# Sheet2_old.net
KiCad netlist of a schematic drawn in Altium Designer
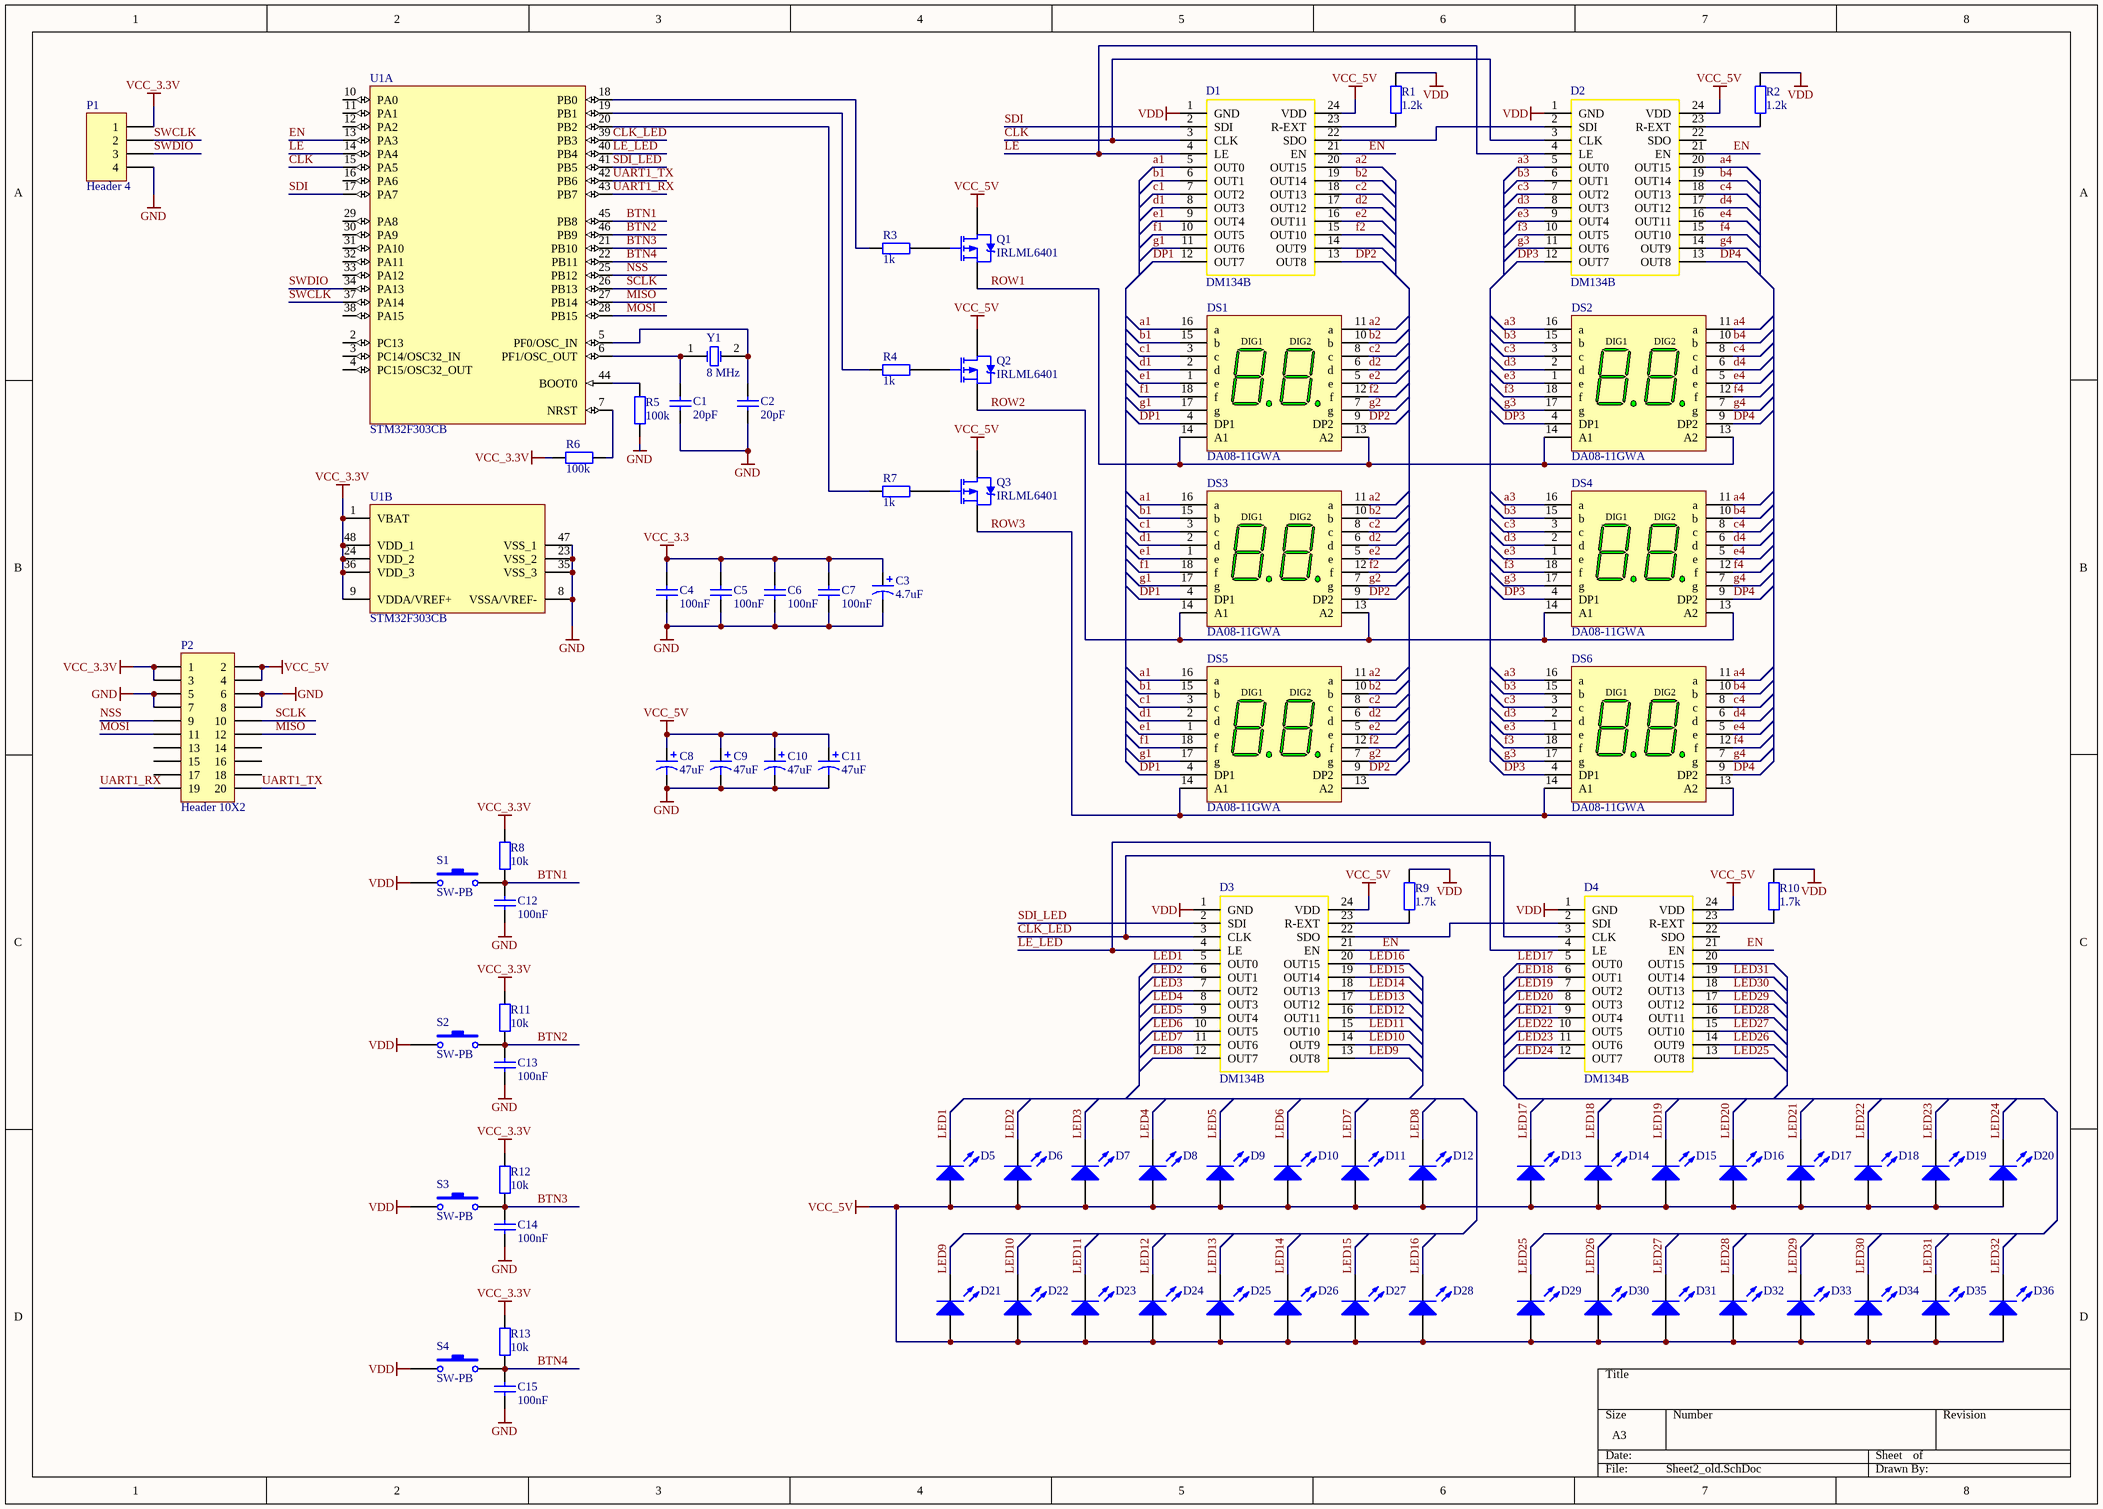
[diagram p0: Sheet2_old.SchDoc]

(export (version "E")
  (design (tool "Eeschema 10.0.6"))
  (components
    (comp (ref "C1")
      (value "20pF")
      (footprint "RAD-0.3")
      (description "Capacitor")
      (fields (field (name "PUBLISHER") "Altium Limited"))
      (libsource (lib "Miscellaneous Devices") (part "Cap"))
    )
    (comp (ref "C2")
      (value "20pF")
      (footprint "RAD-0.3")
      (description "Capacitor")
      (fields (field (name "PUBLISHER") "Altium Limited"))
      (libsource (lib "Miscellaneous Devices") (part "Cap"))
    )
    (comp (ref "C3")
      (value "4.7uF")
      (footprint "RB7.6-15")
      (description "Polarized Capacitor (Radial)")
      (fields (field (name "PUBLISHER") "Altium Limited"))
      (libsource (lib "Miscellaneous Devices") (part "Cap Pol1"))
    )
    (comp (ref "C4")
      (value "100nF")
      (footprint "RAD-0.3")
      (description "Capacitor")
      (fields (field (name "PUBLISHER") "Altium Limited"))
      (libsource (lib "Miscellaneous Devices") (part "Cap"))
    )
    (comp (ref "C5")
      (value "100nF")
      (footprint "RAD-0.3")
      (description "Capacitor")
      (fields (field (name "PUBLISHER") "Altium Limited"))
      (libsource (lib "Miscellaneous Devices") (part "Cap"))
    )
    (comp (ref "C6")
      (value "100nF")
      (footprint "RAD-0.3")
      (description "Capacitor")
      (fields (field (name "PUBLISHER") "Altium Limited"))
      (libsource (lib "Miscellaneous Devices") (part "Cap"))
    )
    (comp (ref "C7")
      (value "100nF")
      (footprint "RAD-0.3")
      (description "Capacitor")
      (fields (field (name "PUBLISHER") "Altium Limited"))
      (libsource (lib "Miscellaneous Devices") (part "Cap"))
    )
    (comp (ref "C8")
      (value "47uF")
      (footprint "RB7.6-15")
      (description "Polarized Capacitor (Radial)")
      (fields (field (name "PUBLISHER") "Altium Limited"))
      (libsource (lib "Miscellaneous Devices") (part "Cap Pol1"))
    )
    (comp (ref "C9")
      (value "47uF")
      (footprint "RB7.6-15")
      (description "Polarized Capacitor (Radial)")
      (fields (field (name "PUBLISHER") "Altium Limited"))
      (libsource (lib "Miscellaneous Devices") (part "Cap Pol1"))
    )
    (comp (ref "C10")
      (value "47uF")
      (footprint "RB7.6-15")
      (description "Polarized Capacitor (Radial)")
      (fields (field (name "PUBLISHER") "Altium Limited"))
      (libsource (lib "Miscellaneous Devices") (part "Cap Pol1"))
    )
    (comp (ref "C11")
      (value "47uF")
      (footprint "RB7.6-15")
      (description "Polarized Capacitor (Radial)")
      (fields (field (name "PUBLISHER") "Altium Limited"))
      (libsource (lib "Miscellaneous Devices") (part "Cap Pol1"))
    )
    (comp (ref "C12")
      (value "100nF")
      (footprint "RAD-0.3")
      (description "Capacitor")
      (fields (field (name "PUBLISHER") "Altium Limited"))
      (libsource (lib "Miscellaneous Devices") (part "Cap"))
    )
    (comp (ref "C13")
      (value "100nF")
      (footprint "RAD-0.3")
      (description "Capacitor")
      (fields (field (name "PUBLISHER") "Altium Limited"))
      (libsource (lib "Miscellaneous Devices") (part "Cap"))
    )
    (comp (ref "C14")
      (value "100nF")
      (footprint "RAD-0.3")
      (description "Capacitor")
      (fields (field (name "PUBLISHER") "Altium Limited"))
      (libsource (lib "Miscellaneous Devices") (part "Cap"))
    )
    (comp (ref "C15")
      (value "100nF")
      (footprint "RAD-0.3")
      (description "Capacitor")
      (fields (field (name "PUBLISHER") "Altium Limited"))
      (libsource (lib "Miscellaneous Devices") (part "Cap"))
    )
    (comp (ref "D1")
      (value "DM134B")
      (description "LED Driver")
      (libsource (lib "Sektor_LED_Drivers") (part "DM134B"))
    )
    (comp (ref "D2")
      (value "DM134B")
      (description "LED Driver")
      (libsource (lib "Sektor_LED_Drivers") (part "DM134B"))
    )
    (comp (ref "D3")
      (value "DM134B")
      (description "LED Driver")
      (libsource (lib "Sektor_LED_Drivers") (part "DM134B"))
    )
    (comp (ref "D4")
      (value "DM134B")
      (description "LED Driver")
      (libsource (lib "Sektor_LED_Drivers") (part "DM134B"))
    )
    (comp (ref "D5")
      (value "LED0")
      (footprint "LED-0")
      (description "Typical INFRARED GaAs LED")
      (fields (field (name "PUBLISHER") "Altium Limited"))
      (libsource (lib "Miscellaneous Devices") (part "LED0"))
    )
    (comp (ref "D6")
      (value "LED0")
      (footprint "LED-0")
      (description "Typical INFRARED GaAs LED")
      (fields (field (name "PUBLISHER") "Altium Limited"))
      (libsource (lib "Miscellaneous Devices") (part "LED0"))
    )
    (comp (ref "D7")
      (value "LED0")
      (footprint "LED-0")
      (description "Typical INFRARED GaAs LED")
      (fields (field (name "PUBLISHER") "Altium Limited"))
      (libsource (lib "Miscellaneous Devices") (part "LED0"))
    )
    (comp (ref "D8")
      (value "LED0")
      (footprint "LED-0")
      (description "Typical INFRARED GaAs LED")
      (fields (field (name "PUBLISHER") "Altium Limited"))
      (libsource (lib "Miscellaneous Devices") (part "LED0"))
    )
    (comp (ref "D9")
      (value "LED0")
      (footprint "LED-0")
      (description "Typical INFRARED GaAs LED")
      (fields (field (name "PUBLISHER") "Altium Limited"))
      (libsource (lib "Miscellaneous Devices") (part "LED0"))
    )
    (comp (ref "D10")
      (value "LED0")
      (footprint "LED-0")
      (description "Typical INFRARED GaAs LED")
      (fields (field (name "PUBLISHER") "Altium Limited"))
      (libsource (lib "Miscellaneous Devices") (part "LED0"))
    )
    (comp (ref "D11")
      (value "LED0")
      (footprint "LED-0")
      (description "Typical INFRARED GaAs LED")
      (fields (field (name "PUBLISHER") "Altium Limited"))
      (libsource (lib "Miscellaneous Devices") (part "LED0"))
    )
    (comp (ref "D12")
      (value "LED0")
      (footprint "LED-0")
      (description "Typical INFRARED GaAs LED")
      (fields (field (name "PUBLISHER") "Altium Limited"))
      (libsource (lib "Miscellaneous Devices") (part "LED0"))
    )
    (comp (ref "D13")
      (value "LED0")
      (footprint "LED-0")
      (description "Typical INFRARED GaAs LED")
      (fields (field (name "PUBLISHER") "Altium Limited"))
      (libsource (lib "Miscellaneous Devices") (part "LED0"))
    )
    (comp (ref "D14")
      (value "LED0")
      (footprint "LED-0")
      (description "Typical INFRARED GaAs LED")
      (fields (field (name "PUBLISHER") "Altium Limited"))
      (libsource (lib "Miscellaneous Devices") (part "LED0"))
    )
    (comp (ref "D15")
      (value "LED0")
      (footprint "LED-0")
      (description "Typical INFRARED GaAs LED")
      (fields (field (name "PUBLISHER") "Altium Limited"))
      (libsource (lib "Miscellaneous Devices") (part "LED0"))
    )
    (comp (ref "D16")
      (value "LED0")
      (footprint "LED-0")
      (description "Typical INFRARED GaAs LED")
      (fields (field (name "PUBLISHER") "Altium Limited"))
      (libsource (lib "Miscellaneous Devices") (part "LED0"))
    )
    (comp (ref "D17")
      (value "LED0")
      (footprint "LED-0")
      (description "Typical INFRARED GaAs LED")
      (fields (field (name "PUBLISHER") "Altium Limited"))
      (libsource (lib "Miscellaneous Devices") (part "LED0"))
    )
    (comp (ref "D18")
      (value "LED0")
      (footprint "LED-0")
      (description "Typical INFRARED GaAs LED")
      (fields (field (name "PUBLISHER") "Altium Limited"))
      (libsource (lib "Miscellaneous Devices") (part "LED0"))
    )
    (comp (ref "D19")
      (value "LED0")
      (footprint "LED-0")
      (description "Typical INFRARED GaAs LED")
      (fields (field (name "PUBLISHER") "Altium Limited"))
      (libsource (lib "Miscellaneous Devices") (part "LED0"))
    )
    (comp (ref "D20")
      (value "LED0")
      (footprint "LED-0")
      (description "Typical INFRARED GaAs LED")
      (fields (field (name "PUBLISHER") "Altium Limited"))
      (libsource (lib "Miscellaneous Devices") (part "LED0"))
    )
    (comp (ref "D21")
      (value "LED0")
      (footprint "LED-0")
      (description "Typical INFRARED GaAs LED")
      (fields (field (name "PUBLISHER") "Altium Limited"))
      (libsource (lib "Miscellaneous Devices") (part "LED0"))
    )
    (comp (ref "D22")
      (value "LED0")
      (footprint "LED-0")
      (description "Typical INFRARED GaAs LED")
      (fields (field (name "PUBLISHER") "Altium Limited"))
      (libsource (lib "Miscellaneous Devices") (part "LED0"))
    )
    (comp (ref "D23")
      (value "LED0")
      (footprint "LED-0")
      (description "Typical INFRARED GaAs LED")
      (fields (field (name "PUBLISHER") "Altium Limited"))
      (libsource (lib "Miscellaneous Devices") (part "LED0"))
    )
    (comp (ref "D24")
      (value "LED0")
      (footprint "LED-0")
      (description "Typical INFRARED GaAs LED")
      (fields (field (name "PUBLISHER") "Altium Limited"))
      (libsource (lib "Miscellaneous Devices") (part "LED0"))
    )
    (comp (ref "D25")
      (value "LED0")
      (footprint "LED-0")
      (description "Typical INFRARED GaAs LED")
      (fields (field (name "PUBLISHER") "Altium Limited"))
      (libsource (lib "Miscellaneous Devices") (part "LED0"))
    )
    (comp (ref "D26")
      (value "LED0")
      (footprint "LED-0")
      (description "Typical INFRARED GaAs LED")
      (fields (field (name "PUBLISHER") "Altium Limited"))
      (libsource (lib "Miscellaneous Devices") (part "LED0"))
    )
    (comp (ref "D27")
      (value "LED0")
      (footprint "LED-0")
      (description "Typical INFRARED GaAs LED")
      (fields (field (name "PUBLISHER") "Altium Limited"))
      (libsource (lib "Miscellaneous Devices") (part "LED0"))
    )
    (comp (ref "D28")
      (value "LED0")
      (footprint "LED-0")
      (description "Typical INFRARED GaAs LED")
      (fields (field (name "PUBLISHER") "Altium Limited"))
      (libsource (lib "Miscellaneous Devices") (part "LED0"))
    )
    (comp (ref "D29")
      (value "LED0")
      (footprint "LED-0")
      (description "Typical INFRARED GaAs LED")
      (fields (field (name "PUBLISHER") "Altium Limited"))
      (libsource (lib "Miscellaneous Devices") (part "LED0"))
    )
    (comp (ref "D30")
      (value "LED0")
      (footprint "LED-0")
      (description "Typical INFRARED GaAs LED")
      (fields (field (name "PUBLISHER") "Altium Limited"))
      (libsource (lib "Miscellaneous Devices") (part "LED0"))
    )
    (comp (ref "D31")
      (value "LED0")
      (footprint "LED-0")
      (description "Typical INFRARED GaAs LED")
      (fields (field (name "PUBLISHER") "Altium Limited"))
      (libsource (lib "Miscellaneous Devices") (part "LED0"))
    )
    (comp (ref "D32")
      (value "LED0")
      (footprint "LED-0")
      (description "Typical INFRARED GaAs LED")
      (fields (field (name "PUBLISHER") "Altium Limited"))
      (libsource (lib "Miscellaneous Devices") (part "LED0"))
    )
    (comp (ref "D33")
      (value "LED0")
      (footprint "LED-0")
      (description "Typical INFRARED GaAs LED")
      (fields (field (name "PUBLISHER") "Altium Limited"))
      (libsource (lib "Miscellaneous Devices") (part "LED0"))
    )
    (comp (ref "D34")
      (value "LED0")
      (footprint "LED-0")
      (description "Typical INFRARED GaAs LED")
      (fields (field (name "PUBLISHER") "Altium Limited"))
      (libsource (lib "Miscellaneous Devices") (part "LED0"))
    )
    (comp (ref "D35")
      (value "LED0")
      (footprint "LED-0")
      (description "Typical INFRARED GaAs LED")
      (fields (field (name "PUBLISHER") "Altium Limited"))
      (libsource (lib "Miscellaneous Devices") (part "LED0"))
    )
    (comp (ref "D36")
      (value "LED0")
      (footprint "LED-0")
      (description "Typical INFRARED GaAs LED")
      (fields (field (name "PUBLISHER") "Altium Limited"))
      (libsource (lib "Miscellaneous Devices") (part "LED0"))
    )
    (comp (ref "DS1")
      (value "DA08-11GWA")
      (description "Двухсимвольный светодиодный индикатор")
      (libsource (lib "Sektor_LED_Displays") (part "DA08-11GWA"))
    )
    (comp (ref "DS2")
      (value "DA08-11GWA")
      (description "Двухсимвольный светодиодный индикатор")
      (libsource (lib "Sektor_LED_Displays") (part "DA08-11GWA"))
    )
    (comp (ref "DS3")
      (value "DA08-11GWA")
      (description "Двухсимвольный светодиодный индикатор")
      (libsource (lib "Sektor_LED_Displays") (part "DA08-11GWA"))
    )
    (comp (ref "DS4")
      (value "DA08-11GWA")
      (description "Двухсимвольный светодиодный индикатор")
      (libsource (lib "Sektor_LED_Displays") (part "DA08-11GWA"))
    )
    (comp (ref "DS5")
      (value "DA08-11GWA")
      (description "Двухсимвольный светодиодный индикатор")
      (libsource (lib "Sektor_LED_Displays") (part "DA08-11GWA"))
    )
    (comp (ref "DS6")
      (value "DA08-11GWA")
      (description "Двухсимвольный светодиодный индикатор")
      (libsource (lib "Sektor_LED_Displays") (part "DA08-11GWA"))
    )
    (comp (ref "P1")
      (value "Header 4")
      (footprint "HDR1X4")
      (description "Header, 4-Pin")
      (fields (field (name "PUBLISHER") "Altium Limited"))
      (libsource (lib "Miscellaneous Connectors") (part "Header 4"))
    )
    (comp (ref "P2")
      (value "Header 10X2")
      (footprint "HDR2X10")
      (description "Header, 10-Pin, Dual row")
      (fields (field (name "PUBLISHER") "Altium Limited"))
      (libsource (lib "Miscellaneous Connectors") (part "Header 10X2"))
    )
    (comp (ref "Q1")
      (value "IRLML6401")
      (footprint "TO-220AB")
      (description "P-Channel Power MOSFET")
      (fields (field (name "PUBLISHER") "Altium Limited"))
      (libsource (lib "Miscellaneous Devices") (part "PMOS-2"))
    )
    (comp (ref "Q2")
      (value "IRLML6401")
      (footprint "TO-220AB")
      (description "P-Channel Power MOSFET")
      (fields (field (name "PUBLISHER") "Altium Limited"))
      (libsource (lib "Miscellaneous Devices") (part "PMOS-2"))
    )
    (comp (ref "Q3")
      (value "IRLML6401")
      (footprint "TO-220AB")
      (description "P-Channel Power MOSFET")
      (fields (field (name "PUBLISHER") "Altium Limited"))
      (libsource (lib "Miscellaneous Devices") (part "PMOS-2"))
    )
    (comp (ref "R1")
      (value "1.2k")
      (footprint "AXIAL-0.4")
      (description "Resistor")
      (fields (field (name "PUBLISHER") "Altium Limited"))
      (libsource (lib "") (part "Res2_1"))
    )
    (comp (ref "R2")
      (value "1.2k")
      (footprint "AXIAL-0.4")
      (description "Resistor")
      (fields (field (name "PUBLISHER") "Altium Limited"))
      (libsource (lib "") (part "Res2_1"))
    )
    (comp (ref "R3")
      (value "1k")
      (footprint "AXIAL-0.4")
      (description "Resistor")
      (fields (field (name "PUBLISHER") "Altium Limited"))
      (libsource (lib "") (part "Res2_2"))
    )
    (comp (ref "R4")
      (value "1k")
      (footprint "AXIAL-0.4")
      (description "Resistor")
      (fields (field (name "PUBLISHER") "Altium Limited"))
      (libsource (lib "") (part "Res2_2"))
    )
    (comp (ref "R5")
      (value "100k")
      (footprint "AXIAL-0.4")
      (description "Resistor")
      (fields (field (name "PUBLISHER") "Altium Limited"))
      (libsource (lib "Miscellaneous Devices") (part "Res2"))
    )
    (comp (ref "R6")
      (value "100k")
      (footprint "AXIAL-0.4")
      (description "Resistor")
      (fields (field (name "PUBLISHER") "Altium Limited"))
      (libsource (lib "") (part "Res2_2"))
    )
    (comp (ref "R7")
      (value "1k")
      (footprint "AXIAL-0.4")
      (description "Resistor")
      (fields (field (name "PUBLISHER") "Altium Limited"))
      (libsource (lib "") (part "Res2_2"))
    )
    (comp (ref "R8")
      (value "10k")
      (footprint "AXIAL-0.4")
      (description "Resistor")
      (fields (field (name "PUBLISHER") "Altium Limited"))
      (libsource (lib "") (part "Res2_3"))
    )
    (comp (ref "R9")
      (value "1.7k")
      (footprint "AXIAL-0.4")
      (description "Resistor")
      (fields (field (name "PUBLISHER") "Altium Limited"))
      (libsource (lib "") (part "Res2_1"))
    )
    (comp (ref "R10")
      (value "1.7k")
      (footprint "AXIAL-0.4")
      (description "Resistor")
      (fields (field (name "PUBLISHER") "Altium Limited"))
      (libsource (lib "") (part "Res2_1"))
    )
    (comp (ref "R11")
      (value "10k")
      (footprint "AXIAL-0.4")
      (description "Resistor")
      (fields (field (name "PUBLISHER") "Altium Limited"))
      (libsource (lib "") (part "Res2_3"))
    )
    (comp (ref "R12")
      (value "10k")
      (footprint "AXIAL-0.4")
      (description "Resistor")
      (fields (field (name "PUBLISHER") "Altium Limited"))
      (libsource (lib "") (part "Res2_3"))
    )
    (comp (ref "R13")
      (value "10k")
      (footprint "AXIAL-0.4")
      (description "Resistor")
      (fields (field (name "PUBLISHER") "Altium Limited"))
      (libsource (lib "") (part "Res2_3"))
    )
    (comp (ref "S1")
      (value "SW-PB")
      (footprint "SPST-2")
      (description "Switch")
      (fields (field (name "PUBLISHER") "Altium Limited"))
      (libsource (lib "Miscellaneous Devices") (part "SW-PB"))
    )
    (comp (ref "S2")
      (value "SW-PB")
      (footprint "SPST-2")
      (description "Switch")
      (fields (field (name "PUBLISHER") "Altium Limited"))
      (libsource (lib "Miscellaneous Devices") (part "SW-PB"))
    )
    (comp (ref "S3")
      (value "SW-PB")
      (footprint "SPST-2")
      (description "Switch")
      (fields (field (name "PUBLISHER") "Altium Limited"))
      (libsource (lib "Miscellaneous Devices") (part "SW-PB"))
    )
    (comp (ref "S4")
      (value "SW-PB")
      (footprint "SPST-2")
      (description "Switch")
      (fields (field (name "PUBLISHER") "Altium Limited"))
      (libsource (lib "Miscellaneous Devices") (part "SW-PB"))
    )
    (comp (ref "U1")
      (value "STM32F303CB")
      (footprint "LQFP48_M")
      (libsource (lib "Sektor_STMicroelectronics_STM32F3") (part "STM32F303CB"))
    )
    (comp (ref "Y1")
      (value "8 MHz")
      (footprint "R38")
      (description "Crystal Oscillator")
      (fields (field (name "PUBLISHER") "Altium Limited"))
      (libsource (lib "Miscellaneous Devices") (part "XTAL"))
    )
  )
  (nets
    (net (code "1") (name "/BTN1") (class "Default")
      (node (ref "C12") (pin "2") (pinfunction "2_2") (pintype "passive"))
      (node (ref "R8") (pin "2") (pinfunction "2_2") (pintype "passive"))
      (node (ref "S1") (pin "1") (pinfunction "1_1") (pintype "passive"))
      (node (ref "U1") (pin "45") (pinfunction "PB8_45") (pintype "bidirectional"))
    )
    (net (code "2") (name "/BTN2") (class "Default")
      (node (ref "C13") (pin "2") (pinfunction "2_2") (pintype "passive"))
      (node (ref "R11") (pin "2") (pinfunction "2_2") (pintype "passive"))
      (node (ref "S2") (pin "1") (pinfunction "1_1") (pintype "passive"))
      (node (ref "U1") (pin "46") (pinfunction "PB9_46") (pintype "bidirectional"))
    )
    (net (code "3") (name "/BTN3") (class "Default")
      (node (ref "C14") (pin "2") (pinfunction "2_2") (pintype "passive"))
      (node (ref "R12") (pin "2") (pinfunction "2_2") (pintype "passive"))
      (node (ref "S3") (pin "1") (pinfunction "1_1") (pintype "passive"))
      (node (ref "U1") (pin "21") (pinfunction "PB10_21") (pintype "bidirectional"))
    )
    (net (code "4") (name "/BTN4") (class "Default")
      (node (ref "C15") (pin "2") (pinfunction "2_2") (pintype "passive"))
      (node (ref "R13") (pin "2") (pinfunction "2_2") (pintype "passive"))
      (node (ref "S4") (pin "1") (pinfunction "1_1") (pintype "passive"))
      (node (ref "U1") (pin "22") (pinfunction "PB11_22") (pintype "bidirectional"))
    )
    (net (code "5") (name "/CLK") (class "Default")
      (node (ref "D1") (pin "3") (pinfunction "CLK_3") (pintype "passive"))
      (node (ref "D2") (pin "3") (pinfunction "CLK_3") (pintype "passive"))
      (node (ref "U1") (pin "15") (pinfunction "PA5_15") (pintype "bidirectional"))
    )
    (net (code "6") (name "/CLK_LED") (class "Default")
      (node (ref "D3") (pin "3") (pinfunction "CLK_3") (pintype "passive"))
      (node (ref "D4") (pin "3") (pinfunction "CLK_3") (pintype "passive"))
      (node (ref "U1") (pin "39") (pinfunction "PB3_39") (pintype "bidirectional"))
    )
    (net (code "7") (name "/DP1") (class "Default")
      (node (ref "D1") (pin "12") (pinfunction "OUT7_12") (pintype "passive"))
      (node (ref "DS1") (pin "4") (pinfunction "DP1_4") (pintype "passive"))
      (node (ref "DS3") (pin "4") (pinfunction "DP1_4") (pintype "passive"))
      (node (ref "DS5") (pin "4") (pinfunction "DP1_4") (pintype "passive"))
    )
    (net (code "8") (name "/DP2") (class "Default")
      (node (ref "D1") (pin "13") (pinfunction "OUT8_13") (pintype "passive"))
      (node (ref "DS1") (pin "9") (pinfunction "DP2_9") (pintype "passive"))
      (node (ref "DS3") (pin "9") (pinfunction "DP2_9") (pintype "passive"))
      (node (ref "DS5") (pin "9") (pinfunction "DP2_9") (pintype "passive"))
    )
    (net (code "9") (name "/DP3") (class "Default")
      (node (ref "D2") (pin "12") (pinfunction "OUT7_12") (pintype "passive"))
      (node (ref "DS2") (pin "4") (pinfunction "DP1_4") (pintype "passive"))
      (node (ref "DS4") (pin "4") (pinfunction "DP1_4") (pintype "passive"))
      (node (ref "DS6") (pin "4") (pinfunction "DP1_4") (pintype "passive"))
    )
    (net (code "10") (name "/DP4") (class "Default")
      (node (ref "D2") (pin "13") (pinfunction "OUT8_13") (pintype "passive"))
      (node (ref "DS2") (pin "9") (pinfunction "DP2_9") (pintype "passive"))
      (node (ref "DS4") (pin "9") (pinfunction "DP2_9") (pintype "passive"))
      (node (ref "DS6") (pin "9") (pinfunction "DP2_9") (pintype "passive"))
    )
    (net (code "11") (name "/EN") (class "Default")
      (node (ref "D1") (pin "21") (pinfunction "EN_21") (pintype "passive"))
      (node (ref "D2") (pin "21") (pinfunction "EN_21") (pintype "passive"))
      (node (ref "D3") (pin "21") (pinfunction "EN_21") (pintype "passive"))
      (node (ref "D4") (pin "21") (pinfunction "EN_21") (pintype "passive"))
      (node (ref "U1") (pin "13") (pinfunction "PA3_13") (pintype "bidirectional"))
    )
    (net (code "12") (name "/LE") (class "Default")
      (node (ref "D1") (pin "4") (pinfunction "LE_4") (pintype "passive"))
      (node (ref "D2") (pin "4") (pinfunction "LE_4") (pintype "passive"))
      (node (ref "U1") (pin "14") (pinfunction "PA4_14") (pintype "bidirectional"))
    )
    (net (code "13") (name "/LED1") (class "Default")
      (node (ref "D3") (pin "5") (pinfunction "OUT0_5") (pintype "passive"))
      (node (ref "D5") (pin "2") (pinfunction "K_2") (pintype "passive"))
    )
    (net (code "14") (name "/LED2") (class "Default")
      (node (ref "D3") (pin "6") (pinfunction "OUT1_6") (pintype "passive"))
      (node (ref "D6") (pin "2") (pinfunction "K_2") (pintype "passive"))
    )
    (net (code "15") (name "/LED3") (class "Default")
      (node (ref "D3") (pin "7") (pinfunction "OUT2_7") (pintype "passive"))
      (node (ref "D7") (pin "2") (pinfunction "K_2") (pintype "passive"))
    )
    (net (code "16") (name "/LED4") (class "Default")
      (node (ref "D3") (pin "8") (pinfunction "OUT3_8") (pintype "passive"))
      (node (ref "D8") (pin "2") (pinfunction "K_2") (pintype "passive"))
    )
    (net (code "17") (name "/LED5") (class "Default")
      (node (ref "D3") (pin "9") (pinfunction "OUT4_9") (pintype "passive"))
      (node (ref "D9") (pin "2") (pinfunction "K_2") (pintype "passive"))
    )
    (net (code "18") (name "/LED6") (class "Default")
      (node (ref "D10") (pin "2") (pinfunction "K_2") (pintype "passive"))
      (node (ref "D3") (pin "10") (pinfunction "OUT5_10") (pintype "passive"))
    )
    (net (code "19") (name "/LED7") (class "Default")
      (node (ref "D11") (pin "2") (pinfunction "K_2") (pintype "passive"))
      (node (ref "D3") (pin "11") (pinfunction "OUT6_11") (pintype "passive"))
    )
    (net (code "20") (name "/LED8") (class "Default")
      (node (ref "D12") (pin "2") (pinfunction "K_2") (pintype "passive"))
      (node (ref "D3") (pin "12") (pinfunction "OUT7_12") (pintype "passive"))
    )
    (net (code "21") (name "/LED9") (class "Default")
      (node (ref "D21") (pin "2") (pinfunction "K_2") (pintype "passive"))
      (node (ref "D3") (pin "13") (pinfunction "OUT8_13") (pintype "passive"))
    )
    (net (code "22") (name "/LED10") (class "Default")
      (node (ref "D22") (pin "2") (pinfunction "K_2") (pintype "passive"))
      (node (ref "D3") (pin "14") (pinfunction "OUT9_14") (pintype "passive"))
    )
    (net (code "23") (name "/LED11") (class "Default")
      (node (ref "D23") (pin "2") (pinfunction "K_2") (pintype "passive"))
      (node (ref "D3") (pin "15") (pinfunction "OUT10_15") (pintype "passive"))
    )
    (net (code "24") (name "/LED12") (class "Default")
      (node (ref "D24") (pin "2") (pinfunction "K_2") (pintype "passive"))
      (node (ref "D3") (pin "16") (pinfunction "OUT11_16") (pintype "passive"))
    )
    (net (code "25") (name "/LED13") (class "Default")
      (node (ref "D25") (pin "2") (pinfunction "K_2") (pintype "passive"))
      (node (ref "D3") (pin "17") (pinfunction "OUT12_17") (pintype "passive"))
    )
    (net (code "26") (name "/LED14") (class "Default")
      (node (ref "D26") (pin "2") (pinfunction "K_2") (pintype "passive"))
      (node (ref "D3") (pin "18") (pinfunction "OUT13_18") (pintype "passive"))
    )
    (net (code "27") (name "/LED15") (class "Default")
      (node (ref "D27") (pin "2") (pinfunction "K_2") (pintype "passive"))
      (node (ref "D3") (pin "19") (pinfunction "OUT14_19") (pintype "passive"))
    )
    (net (code "28") (name "/LED16") (class "Default")
      (node (ref "D28") (pin "2") (pinfunction "K_2") (pintype "passive"))
      (node (ref "D3") (pin "20") (pinfunction "OUT15_20") (pintype "passive"))
    )
    (net (code "29") (name "/LED17") (class "Default")
      (node (ref "D13") (pin "2") (pinfunction "K_2") (pintype "passive"))
      (node (ref "D4") (pin "5") (pinfunction "OUT0_5") (pintype "passive"))
    )
    (net (code "30") (name "/LED18") (class "Default")
      (node (ref "D14") (pin "2") (pinfunction "K_2") (pintype "passive"))
      (node (ref "D4") (pin "6") (pinfunction "OUT1_6") (pintype "passive"))
    )
    (net (code "31") (name "/LED19") (class "Default")
      (node (ref "D15") (pin "2") (pinfunction "K_2") (pintype "passive"))
      (node (ref "D4") (pin "7") (pinfunction "OUT2_7") (pintype "passive"))
    )
    (net (code "32") (name "/LED20") (class "Default")
      (node (ref "D16") (pin "2") (pinfunction "K_2") (pintype "passive"))
      (node (ref "D4") (pin "8") (pinfunction "OUT3_8") (pintype "passive"))
    )
    (net (code "33") (name "/LED21") (class "Default")
      (node (ref "D17") (pin "2") (pinfunction "K_2") (pintype "passive"))
      (node (ref "D4") (pin "9") (pinfunction "OUT4_9") (pintype "passive"))
    )
    (net (code "34") (name "/LED22") (class "Default")
      (node (ref "D18") (pin "2") (pinfunction "K_2") (pintype "passive"))
      (node (ref "D4") (pin "10") (pinfunction "OUT5_10") (pintype "passive"))
    )
    (net (code "35") (name "/LED23") (class "Default")
      (node (ref "D19") (pin "2") (pinfunction "K_2") (pintype "passive"))
      (node (ref "D4") (pin "11") (pinfunction "OUT6_11") (pintype "passive"))
    )
    (net (code "36") (name "/LED24") (class "Default")
      (node (ref "D20") (pin "2") (pinfunction "K_2") (pintype "passive"))
      (node (ref "D4") (pin "12") (pinfunction "OUT7_12") (pintype "passive"))
    )
    (net (code "37") (name "/LED25") (class "Default")
      (node (ref "D29") (pin "2") (pinfunction "K_2") (pintype "passive"))
      (node (ref "D4") (pin "13") (pinfunction "OUT8_13") (pintype "passive"))
    )
    (net (code "38") (name "/LED26") (class "Default")
      (node (ref "D30") (pin "2") (pinfunction "K_2") (pintype "passive"))
      (node (ref "D4") (pin "14") (pinfunction "OUT9_14") (pintype "passive"))
    )
    (net (code "39") (name "/LED27") (class "Default")
      (node (ref "D31") (pin "2") (pinfunction "K_2") (pintype "passive"))
      (node (ref "D4") (pin "15") (pinfunction "OUT10_15") (pintype "passive"))
    )
    (net (code "40") (name "/LED28") (class "Default")
      (node (ref "D32") (pin "2") (pinfunction "K_2") (pintype "passive"))
      (node (ref "D4") (pin "16") (pinfunction "OUT11_16") (pintype "passive"))
    )
    (net (code "41") (name "/LED29") (class "Default")
      (node (ref "D33") (pin "2") (pinfunction "K_2") (pintype "passive"))
      (node (ref "D4") (pin "17") (pinfunction "OUT12_17") (pintype "passive"))
    )
    (net (code "42") (name "/LED30") (class "Default")
      (node (ref "D34") (pin "2") (pinfunction "K_2") (pintype "passive"))
      (node (ref "D4") (pin "18") (pinfunction "OUT13_18") (pintype "passive"))
    )
    (net (code "43") (name "/LED31") (class "Default")
      (node (ref "D35") (pin "2") (pinfunction "K_2") (pintype "passive"))
      (node (ref "D4") (pin "19") (pinfunction "OUT14_19") (pintype "passive"))
    )
    (net (code "44") (name "/LED32") (class "Default")
      (node (ref "D36") (pin "2") (pinfunction "K_2") (pintype "passive"))
    )
    (net (code "45") (name "/LE_LED") (class "Default")
      (node (ref "D3") (pin "4") (pinfunction "LE_4") (pintype "passive"))
      (node (ref "D4") (pin "4") (pinfunction "LE_4") (pintype "passive"))
      (node (ref "U1") (pin "40") (pinfunction "PB4_40") (pintype "bidirectional"))
    )
    (net (code "46") (name "/MISO") (class "Default")
      (node (ref "P2") (pin "12") (pinfunction "12_12") (pintype "passive"))
      (node (ref "U1") (pin "27") (pinfunction "PB14_27") (pintype "bidirectional"))
    )
    (net (code "47") (name "/MOSI") (class "Default")
      (node (ref "P2") (pin "11") (pinfunction "11_11") (pintype "passive"))
      (node (ref "U1") (pin "28") (pinfunction "PB15_28") (pintype "bidirectional"))
    )
    (net (code "48") (name "/NSS") (class "Default")
      (node (ref "P2") (pin "9") (pinfunction "9_9") (pintype "passive"))
      (node (ref "U1") (pin "25") (pinfunction "PB12_25") (pintype "bidirectional"))
    )
    (net (code "49") (name "/ROW1") (class "Default")
      (node (ref "DS1") (pin "13") (pinfunction "A2_13") (pintype "passive"))
      (node (ref "DS1") (pin "14") (pinfunction "A1_14") (pintype "passive"))
      (node (ref "DS2") (pin "13") (pinfunction "A2_13") (pintype "passive"))
      (node (ref "DS2") (pin "14") (pinfunction "A1_14") (pintype "passive"))
      (node (ref "Q1") (pin "3") (pinfunction "S_3") (pintype "passive"))
    )
    (net (code "50") (name "/ROW2") (class "Default")
      (node (ref "DS3") (pin "13") (pinfunction "A2_13") (pintype "passive"))
      (node (ref "DS3") (pin "14") (pinfunction "A1_14") (pintype "passive"))
      (node (ref "DS4") (pin "13") (pinfunction "A2_13") (pintype "passive"))
      (node (ref "DS4") (pin "14") (pinfunction "A1_14") (pintype "passive"))
      (node (ref "Q2") (pin "3") (pinfunction "S_3") (pintype "passive"))
    )
    (net (code "51") (name "/ROW3") (class "Default")
      (node (ref "DS5") (pin "14") (pinfunction "A1_14") (pintype "passive"))
      (node (ref "DS6") (pin "13") (pinfunction "A2_13") (pintype "passive"))
      (node (ref "DS6") (pin "14") (pinfunction "A1_14") (pintype "passive"))
      (node (ref "Q3") (pin "3") (pinfunction "S_3") (pintype "passive"))
    )
    (net (code "52") (name "/SCLK") (class "Default")
      (node (ref "P2") (pin "10") (pinfunction "10_10") (pintype "passive"))
      (node (ref "U1") (pin "26") (pinfunction "PB13_26") (pintype "bidirectional"))
    )
    (net (code "53") (name "/SDI") (class "Default")
      (node (ref "D1") (pin "2") (pinfunction "SDI_2") (pintype "passive"))
      (node (ref "U1") (pin "17") (pinfunction "PA7_17") (pintype "bidirectional"))
    )
    (net (code "54") (name "/SDI_LED") (class "Default")
      (node (ref "D3") (pin "2") (pinfunction "SDI_2") (pintype "passive"))
      (node (ref "U1") (pin "41") (pinfunction "PB5_41") (pintype "bidirectional"))
    )
    (net (code "55") (name "/SWCLK") (class "Default")
      (node (ref "P1") (pin "2") (pinfunction "2_2") (pintype "passive"))
      (node (ref "U1") (pin "37") (pinfunction "PA14_37") (pintype "bidirectional"))
    )
    (net (code "56") (name "/SWDIO") (class "Default")
      (node (ref "P1") (pin "3") (pinfunction "3_3") (pintype "passive"))
      (node (ref "U1") (pin "34") (pinfunction "PA13_34") (pintype "bidirectional"))
    )
    (net (code "57") (name "/UART1_RX") (class "Default")
      (node (ref "P2") (pin "19") (pinfunction "19_19") (pintype "passive"))
      (node (ref "U1") (pin "43") (pinfunction "PB7_43") (pintype "bidirectional"))
    )
    (net (code "58") (name "/UART1_TX") (class "Default")
      (node (ref "P2") (pin "20") (pinfunction "20_20") (pintype "passive"))
      (node (ref "U1") (pin "42") (pinfunction "PB6_42") (pintype "bidirectional"))
    )
    (net (code "59") (name "/a1") (class "Default")
      (node (ref "D1") (pin "5") (pinfunction "OUT0_5") (pintype "passive"))
      (node (ref "DS1") (pin "16") (pinfunction "a_16") (pintype "passive"))
      (node (ref "DS3") (pin "16") (pinfunction "a_16") (pintype "passive"))
      (node (ref "DS5") (pin "16") (pinfunction "a_16") (pintype "passive"))
    )
    (net (code "60") (name "/a2") (class "Default")
      (node (ref "D1") (pin "20") (pinfunction "OUT15_20") (pintype "passive"))
      (node (ref "DS1") (pin "11") (pinfunction "a_11") (pintype "passive"))
      (node (ref "DS3") (pin "11") (pinfunction "a_11") (pintype "passive"))
      (node (ref "DS5") (pin "11") (pinfunction "a_11") (pintype "passive"))
    )
    (net (code "61") (name "/a3") (class "Default")
      (node (ref "D2") (pin "5") (pinfunction "OUT0_5") (pintype "passive"))
      (node (ref "DS2") (pin "16") (pinfunction "a_16") (pintype "passive"))
      (node (ref "DS4") (pin "16") (pinfunction "a_16") (pintype "passive"))
      (node (ref "DS6") (pin "16") (pinfunction "a_16") (pintype "passive"))
    )
    (net (code "62") (name "/a4") (class "Default")
      (node (ref "D2") (pin "20") (pinfunction "OUT15_20") (pintype "passive"))
      (node (ref "DS2") (pin "11") (pinfunction "a_11") (pintype "passive"))
      (node (ref "DS4") (pin "11") (pinfunction "a_11") (pintype "passive"))
      (node (ref "DS6") (pin "11") (pinfunction "a_11") (pintype "passive"))
    )
    (net (code "63") (name "/b1") (class "Default")
      (node (ref "D1") (pin "6") (pinfunction "OUT1_6") (pintype "passive"))
      (node (ref "DS1") (pin "15") (pinfunction "b_15") (pintype "passive"))
      (node (ref "DS3") (pin "15") (pinfunction "b_15") (pintype "passive"))
      (node (ref "DS5") (pin "15") (pinfunction "b_15") (pintype "passive"))
    )
    (net (code "64") (name "/b2") (class "Default")
      (node (ref "D1") (pin "19") (pinfunction "OUT14_19") (pintype "passive"))
      (node (ref "DS1") (pin "10") (pinfunction "b_10") (pintype "passive"))
      (node (ref "DS3") (pin "10") (pinfunction "b_10") (pintype "passive"))
      (node (ref "DS5") (pin "10") (pinfunction "b_10") (pintype "passive"))
    )
    (net (code "65") (name "/b3") (class "Default")
      (node (ref "D2") (pin "6") (pinfunction "OUT1_6") (pintype "passive"))
      (node (ref "DS2") (pin "15") (pinfunction "b_15") (pintype "passive"))
      (node (ref "DS4") (pin "15") (pinfunction "b_15") (pintype "passive"))
      (node (ref "DS6") (pin "15") (pinfunction "b_15") (pintype "passive"))
    )
    (net (code "66") (name "/b4") (class "Default")
      (node (ref "D2") (pin "19") (pinfunction "OUT14_19") (pintype "passive"))
      (node (ref "DS2") (pin "10") (pinfunction "b_10") (pintype "passive"))
      (node (ref "DS4") (pin "10") (pinfunction "b_10") (pintype "passive"))
      (node (ref "DS6") (pin "10") (pinfunction "b_10") (pintype "passive"))
    )
    (net (code "67") (name "/c1") (class "Default")
      (node (ref "D1") (pin "7") (pinfunction "OUT2_7") (pintype "passive"))
      (node (ref "DS1") (pin "3") (pinfunction "c_3") (pintype "passive"))
      (node (ref "DS3") (pin "3") (pinfunction "c_3") (pintype "passive"))
      (node (ref "DS5") (pin "3") (pinfunction "c_3") (pintype "passive"))
    )
    (net (code "68") (name "/c2") (class "Default")
      (node (ref "D1") (pin "18") (pinfunction "OUT13_18") (pintype "passive"))
      (node (ref "DS1") (pin "8") (pinfunction "c_8") (pintype "passive"))
      (node (ref "DS3") (pin "8") (pinfunction "c_8") (pintype "passive"))
      (node (ref "DS5") (pin "8") (pinfunction "c_8") (pintype "passive"))
    )
    (net (code "69") (name "/c3") (class "Default")
      (node (ref "D2") (pin "7") (pinfunction "OUT2_7") (pintype "passive"))
      (node (ref "DS2") (pin "3") (pinfunction "c_3") (pintype "passive"))
      (node (ref "DS4") (pin "3") (pinfunction "c_3") (pintype "passive"))
      (node (ref "DS6") (pin "3") (pinfunction "c_3") (pintype "passive"))
    )
    (net (code "70") (name "/c4") (class "Default")
      (node (ref "D2") (pin "18") (pinfunction "OUT13_18") (pintype "passive"))
      (node (ref "DS2") (pin "8") (pinfunction "c_8") (pintype "passive"))
      (node (ref "DS4") (pin "8") (pinfunction "c_8") (pintype "passive"))
      (node (ref "DS6") (pin "8") (pinfunction "c_8") (pintype "passive"))
    )
    (net (code "71") (name "/d1") (class "Default")
      (node (ref "D1") (pin "8") (pinfunction "OUT3_8") (pintype "passive"))
      (node (ref "DS1") (pin "2") (pinfunction "d_2") (pintype "passive"))
      (node (ref "DS3") (pin "2") (pinfunction "d_2") (pintype "passive"))
      (node (ref "DS5") (pin "2") (pinfunction "d_2") (pintype "passive"))
    )
    (net (code "72") (name "/d2") (class "Default")
      (node (ref "D1") (pin "17") (pinfunction "OUT12_17") (pintype "passive"))
      (node (ref "DS1") (pin "6") (pinfunction "d_6") (pintype "passive"))
      (node (ref "DS3") (pin "6") (pinfunction "d_6") (pintype "passive"))
      (node (ref "DS5") (pin "6") (pinfunction "d_6") (pintype "passive"))
    )
    (net (code "73") (name "/d3") (class "Default")
      (node (ref "D2") (pin "8") (pinfunction "OUT3_8") (pintype "passive"))
      (node (ref "DS2") (pin "2") (pinfunction "d_2") (pintype "passive"))
      (node (ref "DS4") (pin "2") (pinfunction "d_2") (pintype "passive"))
      (node (ref "DS6") (pin "2") (pinfunction "d_2") (pintype "passive"))
    )
    (net (code "74") (name "/d4") (class "Default")
      (node (ref "D2") (pin "17") (pinfunction "OUT12_17") (pintype "passive"))
      (node (ref "DS2") (pin "6") (pinfunction "d_6") (pintype "passive"))
      (node (ref "DS4") (pin "6") (pinfunction "d_6") (pintype "passive"))
      (node (ref "DS6") (pin "6") (pinfunction "d_6") (pintype "passive"))
    )
    (net (code "75") (name "/e1") (class "Default")
      (node (ref "D1") (pin "9") (pinfunction "OUT4_9") (pintype "passive"))
      (node (ref "DS1") (pin "1") (pinfunction "e_1") (pintype "passive"))
      (node (ref "DS3") (pin "1") (pinfunction "e_1") (pintype "passive"))
      (node (ref "DS5") (pin "1") (pinfunction "e_1") (pintype "passive"))
    )
    (net (code "76") (name "/e2") (class "Default")
      (node (ref "D1") (pin "16") (pinfunction "OUT11_16") (pintype "passive"))
      (node (ref "DS1") (pin "5") (pinfunction "e_5") (pintype "passive"))
      (node (ref "DS3") (pin "5") (pinfunction "e_5") (pintype "passive"))
      (node (ref "DS5") (pin "5") (pinfunction "e_5") (pintype "passive"))
    )
    (net (code "77") (name "/e3") (class "Default")
      (node (ref "D2") (pin "9") (pinfunction "OUT4_9") (pintype "passive"))
      (node (ref "DS2") (pin "1") (pinfunction "e_1") (pintype "passive"))
      (node (ref "DS4") (pin "1") (pinfunction "e_1") (pintype "passive"))
      (node (ref "DS6") (pin "1") (pinfunction "e_1") (pintype "passive"))
    )
    (net (code "78") (name "/e4") (class "Default")
      (node (ref "D2") (pin "16") (pinfunction "OUT11_16") (pintype "passive"))
      (node (ref "DS2") (pin "5") (pinfunction "e_5") (pintype "passive"))
      (node (ref "DS4") (pin "5") (pinfunction "e_5") (pintype "passive"))
      (node (ref "DS6") (pin "5") (pinfunction "e_5") (pintype "passive"))
    )
    (net (code "79") (name "/f1") (class "Default")
      (node (ref "D1") (pin "10") (pinfunction "OUT5_10") (pintype "passive"))
      (node (ref "DS1") (pin "18") (pinfunction "f_18") (pintype "passive"))
      (node (ref "DS3") (pin "18") (pinfunction "f_18") (pintype "passive"))
      (node (ref "DS5") (pin "18") (pinfunction "f_18") (pintype "passive"))
    )
    (net (code "80") (name "/f2") (class "Default")
      (node (ref "D1") (pin "15") (pinfunction "OUT10_15") (pintype "passive"))
      (node (ref "DS1") (pin "12") (pinfunction "f_12") (pintype "passive"))
      (node (ref "DS3") (pin "12") (pinfunction "f_12") (pintype "passive"))
      (node (ref "DS5") (pin "12") (pinfunction "f_12") (pintype "passive"))
    )
    (net (code "81") (name "/f3") (class "Default")
      (node (ref "D2") (pin "10") (pinfunction "OUT5_10") (pintype "passive"))
      (node (ref "DS2") (pin "18") (pinfunction "f_18") (pintype "passive"))
      (node (ref "DS4") (pin "18") (pinfunction "f_18") (pintype "passive"))
      (node (ref "DS6") (pin "18") (pinfunction "f_18") (pintype "passive"))
    )
    (net (code "82") (name "/f4") (class "Default")
      (node (ref "D2") (pin "15") (pinfunction "OUT10_15") (pintype "passive"))
      (node (ref "DS2") (pin "12") (pinfunction "f_12") (pintype "passive"))
      (node (ref "DS4") (pin "12") (pinfunction "f_12") (pintype "passive"))
      (node (ref "DS6") (pin "12") (pinfunction "f_12") (pintype "passive"))
    )
    (net (code "83") (name "/g1") (class "Default")
      (node (ref "D1") (pin "11") (pinfunction "OUT6_11") (pintype "passive"))
      (node (ref "DS1") (pin "17") (pinfunction "g_17") (pintype "passive"))
      (node (ref "DS3") (pin "17") (pinfunction "g_17") (pintype "passive"))
      (node (ref "DS5") (pin "17") (pinfunction "g_17") (pintype "passive"))
    )
    (net (code "84") (name "/g2") (class "Default")
      (node (ref "DS1") (pin "7") (pinfunction "g_7") (pintype "passive"))
      (node (ref "DS3") (pin "7") (pinfunction "g_7") (pintype "passive"))
      (node (ref "DS5") (pin "7") (pinfunction "g_7") (pintype "passive"))
    )
    (net (code "85") (name "/g3") (class "Default")
      (node (ref "D2") (pin "11") (pinfunction "OUT6_11") (pintype "passive"))
      (node (ref "DS2") (pin "17") (pinfunction "g_17") (pintype "passive"))
      (node (ref "DS4") (pin "17") (pinfunction "g_17") (pintype "passive"))
      (node (ref "DS6") (pin "17") (pinfunction "g_17") (pintype "passive"))
    )
    (net (code "86") (name "/g4") (class "Default")
      (node (ref "D2") (pin "14") (pinfunction "OUT9_14") (pintype "passive"))
      (node (ref "DS2") (pin "7") (pinfunction "g_7") (pintype "passive"))
      (node (ref "DS4") (pin "7") (pinfunction "g_7") (pintype "passive"))
      (node (ref "DS6") (pin "7") (pinfunction "g_7") (pintype "passive"))
    )
    (net (code "87") (name "GND") (class "Default")
      (node (ref "C1") (pin "1") (pinfunction "1_1") (pintype "passive"))
      (node (ref "C10") (pin "2") (pinfunction "2_2") (pintype "passive"))
      (node (ref "C11") (pin "2") (pinfunction "2_2") (pintype "passive"))
      (node (ref "C12") (pin "1") (pinfunction "1_1") (pintype "passive"))
      (node (ref "C13") (pin "1") (pinfunction "1_1") (pintype "passive"))
      (node (ref "C14") (pin "1") (pinfunction "1_1") (pintype "passive"))
      (node (ref "C15") (pin "1") (pinfunction "1_1") (pintype "passive"))
      (node (ref "C2") (pin "1") (pinfunction "1_1") (pintype "passive"))
      (node (ref "C3") (pin "2") (pinfunction "2_2") (pintype "passive"))
      (node (ref "C4") (pin "1") (pinfunction "1_1") (pintype "passive"))
      (node (ref "C5") (pin "1") (pinfunction "1_1") (pintype "passive"))
      (node (ref "C6") (pin "1") (pinfunction "1_1") (pintype "passive"))
      (node (ref "C7") (pin "1") (pinfunction "1_1") (pintype "passive"))
      (node (ref "C8") (pin "2") (pinfunction "2_2") (pintype "passive"))
      (node (ref "C9") (pin "2") (pinfunction "2_2") (pintype "passive"))
      (node (ref "P1") (pin "4") (pinfunction "4_4") (pintype "passive"))
      (node (ref "P2") (pin "5") (pinfunction "5_5") (pintype "passive"))
      (node (ref "P2") (pin "6") (pinfunction "6_6") (pintype "passive"))
      (node (ref "P2") (pin "7") (pinfunction "7_7") (pintype "passive"))
      (node (ref "P2") (pin "8") (pinfunction "8_8") (pintype "passive"))
      (node (ref "R5") (pin "1") (pinfunction "1_1") (pintype "passive"))
      (node (ref "U1") (pin "23") (pinfunction "VSS_2_23") (pintype "power_in"))
      (node (ref "U1") (pin "35") (pinfunction "VSS_3_35") (pintype "power_in"))
      (node (ref "U1") (pin "47") (pinfunction "VSS_1_47") (pintype "power_in"))
      (node (ref "U1") (pin "8") (pinfunction "VSSA/VREF-_8") (pintype "power_in"))
    )
    (net (code "88") (name "Net-(D1-R-EXT)") (class "Default")
      (node (ref "D1") (pin "23") (pinfunction "R-EXT_23") (pintype "passive"))
      (node (ref "R1") (pin "2") (pinfunction "2_2") (pintype "passive"))
    )
    (net (code "89") (name "Net-(D1-SDO)") (class "Default")
      (node (ref "D1") (pin "22") (pinfunction "SDO_22") (pintype "passive"))
      (node (ref "D2") (pin "2") (pinfunction "SDI_2") (pintype "passive"))
    )
    (net (code "90") (name "Net-(D2-R-EXT)") (class "Default")
      (node (ref "D2") (pin "23") (pinfunction "R-EXT_23") (pintype "passive"))
      (node (ref "R2") (pin "2") (pinfunction "2_2") (pintype "passive"))
    )
    (net (code "91") (name "Net-(D3-R-EXT)") (class "Default")
      (node (ref "D3") (pin "23") (pinfunction "R-EXT_23") (pintype "passive"))
      (node (ref "R9") (pin "2") (pinfunction "2_2") (pintype "passive"))
    )
    (net (code "92") (name "Net-(D3-SDO)") (class "Default")
      (node (ref "D3") (pin "22") (pinfunction "SDO_22") (pintype "passive"))
      (node (ref "D4") (pin "2") (pinfunction "SDI_2") (pintype "passive"))
    )
    (net (code "93") (name "Net-(D4-R-EXT)") (class "Default")
      (node (ref "D4") (pin "23") (pinfunction "R-EXT_23") (pintype "passive"))
      (node (ref "R10") (pin "2") (pinfunction "2_2") (pintype "passive"))
    )
    (net (code "94") (name "Net-(Q1-G)") (class "Default")
      (node (ref "Q1") (pin "1") (pinfunction "G_1") (pintype "passive"))
      (node (ref "R3") (pin "2") (pinfunction "2_2") (pintype "passive"))
    )
    (net (code "95") (name "Net-(Q2-G)") (class "Default")
      (node (ref "Q2") (pin "1") (pinfunction "G_1") (pintype "passive"))
      (node (ref "R4") (pin "2") (pinfunction "2_2") (pintype "passive"))
    )
    (net (code "96") (name "Net-(Q3-G)") (class "Default")
      (node (ref "Q3") (pin "1") (pinfunction "G_1") (pintype "passive"))
      (node (ref "R7") (pin "2") (pinfunction "2_2") (pintype "passive"))
    )
    (net (code "97") (name "Net-(U1A-BOOT0)") (class "Default")
      (node (ref "R5") (pin "2") (pinfunction "2_2") (pintype "passive"))
      (node (ref "U1") (pin "44") (pinfunction "BOOT0_44") (pintype "input"))
    )
    (net (code "98") (name "Net-(U1A-NRST)") (class "Default")
      (node (ref "R6") (pin "2") (pinfunction "2_2") (pintype "passive"))
      (node (ref "U1") (pin "7") (pinfunction "NRST_7") (pintype "bidirectional"))
    )
    (net (code "99") (name "Net-(U1A-PB0)") (class "Default")
      (node (ref "R3") (pin "1") (pinfunction "1_1") (pintype "passive"))
      (node (ref "U1") (pin "18") (pinfunction "PB0_18") (pintype "bidirectional"))
    )
    (net (code "100") (name "Net-(U1A-PB1)") (class "Default")
      (node (ref "R4") (pin "1") (pinfunction "1_1") (pintype "passive"))
      (node (ref "U1") (pin "19") (pinfunction "PB1_19") (pintype "bidirectional"))
    )
    (net (code "101") (name "Net-(U1A-PB2)") (class "Default")
      (node (ref "R7") (pin "1") (pinfunction "1_1") (pintype "passive"))
      (node (ref "U1") (pin "20") (pinfunction "PB2_20") (pintype "bidirectional"))
    )
    (net (code "102") (name "Net-(U1A-PF0{slash}OSC_IN)") (class "Default")
      (node (ref "C2") (pin "2") (pinfunction "2_2") (pintype "passive"))
      (node (ref "U1") (pin "5") (pinfunction "PF0/OSC_IN_5") (pintype "bidirectional"))
      (node (ref "Y1") (pin "2") (pinfunction "OSC2_2") (pintype "passive"))
    )
    (net (code "103") (name "Net-(U1A-PF1{slash}OSC_OUT)") (class "Default")
      (node (ref "C1") (pin "2") (pinfunction "2_2") (pintype "passive"))
      (node (ref "U1") (pin "6") (pinfunction "PF1/OSC_OUT_6") (pintype "bidirectional"))
      (node (ref "Y1") (pin "1") (pinfunction "OSC1_1") (pintype "passive"))
    )
    (net (code "104") (name "VCC_3.3") (class "Default")
      (node (ref "C3") (pin "1") (pinfunction "1_1") (pintype "passive"))
      (node (ref "C4") (pin "2") (pinfunction "2_2") (pintype "passive"))
      (node (ref "C5") (pin "2") (pinfunction "2_2") (pintype "passive"))
      (node (ref "C6") (pin "2") (pinfunction "2_2") (pintype "passive"))
      (node (ref "C7") (pin "2") (pinfunction "2_2") (pintype "passive"))
    )
    (net (code "105") (name "VCC_3.3V") (class "Default")
      (node (ref "P1") (pin "1") (pinfunction "1_1") (pintype "passive"))
      (node (ref "P2") (pin "1") (pinfunction "1_1") (pintype "passive"))
      (node (ref "P2") (pin "3") (pinfunction "3_3") (pintype "passive"))
      (node (ref "R11") (pin "1") (pinfunction "1_1") (pintype "passive"))
      (node (ref "R12") (pin "1") (pinfunction "1_1") (pintype "passive"))
      (node (ref "R13") (pin "1") (pinfunction "1_1") (pintype "passive"))
      (node (ref "R6") (pin "1") (pinfunction "1_1") (pintype "passive"))
      (node (ref "R8") (pin "1") (pinfunction "1_1") (pintype "passive"))
      (node (ref "U1") (pin "1") (pinfunction "VBAT_1") (pintype "power_in"))
      (node (ref "U1") (pin "24") (pinfunction "VDD_2_24") (pintype "power_in"))
      (node (ref "U1") (pin "36") (pinfunction "VDD_3_36") (pintype "power_in"))
      (node (ref "U1") (pin "48") (pinfunction "VDD_1_48") (pintype "power_in"))
      (node (ref "U1") (pin "9") (pinfunction "VDDA/VREF+_9") (pintype "power_in"))
    )
    (net (code "106") (name "VCC_5V") (class "Default")
      (node (ref "C10") (pin "1") (pinfunction "1_1") (pintype "passive"))
      (node (ref "C11") (pin "1") (pinfunction "1_1") (pintype "passive"))
      (node (ref "C8") (pin "1") (pinfunction "1_1") (pintype "passive"))
      (node (ref "C9") (pin "1") (pinfunction "1_1") (pintype "passive"))
      (node (ref "D1") (pin "24") (pinfunction "VDD_24") (pintype "passive"))
      (node (ref "D10") (pin "1") (pinfunction "A_1") (pintype "passive"))
      (node (ref "D11") (pin "1") (pinfunction "A_1") (pintype "passive"))
      (node (ref "D12") (pin "1") (pinfunction "A_1") (pintype "passive"))
      (node (ref "D13") (pin "1") (pinfunction "A_1") (pintype "passive"))
      (node (ref "D14") (pin "1") (pinfunction "A_1") (pintype "passive"))
      (node (ref "D15") (pin "1") (pinfunction "A_1") (pintype "passive"))
      (node (ref "D16") (pin "1") (pinfunction "A_1") (pintype "passive"))
      (node (ref "D17") (pin "1") (pinfunction "A_1") (pintype "passive"))
      (node (ref "D18") (pin "1") (pinfunction "A_1") (pintype "passive"))
      (node (ref "D19") (pin "1") (pinfunction "A_1") (pintype "passive"))
      (node (ref "D2") (pin "24") (pinfunction "VDD_24") (pintype "passive"))
      (node (ref "D20") (pin "1") (pinfunction "A_1") (pintype "passive"))
      (node (ref "D21") (pin "1") (pinfunction "A_1") (pintype "passive"))
      (node (ref "D22") (pin "1") (pinfunction "A_1") (pintype "passive"))
      (node (ref "D23") (pin "1") (pinfunction "A_1") (pintype "passive"))
      (node (ref "D24") (pin "1") (pinfunction "A_1") (pintype "passive"))
      (node (ref "D25") (pin "1") (pinfunction "A_1") (pintype "passive"))
      (node (ref "D26") (pin "1") (pinfunction "A_1") (pintype "passive"))
      (node (ref "D27") (pin "1") (pinfunction "A_1") (pintype "passive"))
      (node (ref "D28") (pin "1") (pinfunction "A_1") (pintype "passive"))
      (node (ref "D29") (pin "1") (pinfunction "A_1") (pintype "passive"))
      (node (ref "D3") (pin "24") (pinfunction "VDD_24") (pintype "passive"))
      (node (ref "D30") (pin "1") (pinfunction "A_1") (pintype "passive"))
      (node (ref "D31") (pin "1") (pinfunction "A_1") (pintype "passive"))
      (node (ref "D32") (pin "1") (pinfunction "A_1") (pintype "passive"))
      (node (ref "D33") (pin "1") (pinfunction "A_1") (pintype "passive"))
      (node (ref "D34") (pin "1") (pinfunction "A_1") (pintype "passive"))
      (node (ref "D35") (pin "1") (pinfunction "A_1") (pintype "passive"))
      (node (ref "D36") (pin "1") (pinfunction "A_1") (pintype "passive"))
      (node (ref "D4") (pin "24") (pinfunction "VDD_24") (pintype "passive"))
      (node (ref "D5") (pin "1") (pinfunction "A_1") (pintype "passive"))
      (node (ref "D6") (pin "1") (pinfunction "A_1") (pintype "passive"))
      (node (ref "D7") (pin "1") (pinfunction "A_1") (pintype "passive"))
      (node (ref "D8") (pin "1") (pinfunction "A_1") (pintype "passive"))
      (node (ref "D9") (pin "1") (pinfunction "A_1") (pintype "passive"))
      (node (ref "P2") (pin "2") (pinfunction "2_2") (pintype "passive"))
      (node (ref "P2") (pin "4") (pinfunction "4_4") (pintype "passive"))
      (node (ref "Q1") (pin "2") (pinfunction "D_2") (pintype "passive"))
      (node (ref "Q2") (pin "2") (pinfunction "D_2") (pintype "passive"))
      (node (ref "Q3") (pin "2") (pinfunction "D_2") (pintype "passive"))
    )
    (net (code "107") (name "VDD") (class "Default")
      (node (ref "D1") (pin "1") (pinfunction "GND_1") (pintype "passive"))
      (node (ref "D2") (pin "1") (pinfunction "GND_1") (pintype "passive"))
      (node (ref "D3") (pin "1") (pinfunction "GND_1") (pintype "passive"))
      (node (ref "D4") (pin "1") (pinfunction "GND_1") (pintype "passive"))
      (node (ref "R1") (pin "1") (pinfunction "1_1") (pintype "passive"))
      (node (ref "R10") (pin "1") (pinfunction "1_1") (pintype "passive"))
      (node (ref "R2") (pin "1") (pinfunction "1_1") (pintype "passive"))
      (node (ref "R9") (pin "1") (pinfunction "1_1") (pintype "passive"))
      (node (ref "S1") (pin "2") (pinfunction "2_2") (pintype "passive"))
      (node (ref "S2") (pin "2") (pinfunction "2_2") (pintype "passive"))
      (node (ref "S3") (pin "2") (pinfunction "2_2") (pintype "passive"))
      (node (ref "S4") (pin "2") (pinfunction "2_2") (pintype "passive"))
    )
    (net (code "108") (name "unconnected-(D1-OUT9-Pad14)") (class "Default")
      (node (ref "D1") (pin "14") (pinfunction "OUT9_14") (pintype "passive"))
    )
    (net (code "109") (name "unconnected-(D2-SDO-Pad22)") (class "Default")
      (node (ref "D2") (pin "22") (pinfunction "SDO_22") (pintype "passive"))
    )
    (net (code "110") (name "unconnected-(D4-OUT15-Pad20)") (class "Default")
      (node (ref "D4") (pin "20") (pinfunction "OUT15_20") (pintype "passive"))
    )
    (net (code "111") (name "unconnected-(D4-SDO-Pad22)") (class "Default")
      (node (ref "D4") (pin "22") (pinfunction "SDO_22") (pintype "passive"))
    )
    (net (code "112") (name "unconnected-(DS5-A2-Pad13)") (class "Default")
      (node (ref "DS5") (pin "13") (pinfunction "A2_13") (pintype "passive"))
    )
    (net (code "113") (name "unconnected-(P2-Pad13)") (class "Default")
      (node (ref "P2") (pin "13") (pinfunction "13_13") (pintype "passive"))
    )
    (net (code "114") (name "unconnected-(P2-Pad14)") (class "Default")
      (node (ref "P2") (pin "14") (pinfunction "14_14") (pintype "passive"))
    )
    (net (code "115") (name "unconnected-(P2-Pad15)") (class "Default")
      (node (ref "P2") (pin "15") (pinfunction "15_15") (pintype "passive"))
    )
    (net (code "116") (name "unconnected-(P2-Pad16)") (class "Default")
      (node (ref "P2") (pin "16") (pinfunction "16_16") (pintype "passive"))
    )
    (net (code "117") (name "unconnected-(P2-Pad17)") (class "Default")
      (node (ref "P2") (pin "17") (pinfunction "17_17") (pintype "passive"))
    )
    (net (code "118") (name "unconnected-(P2-Pad18)") (class "Default")
      (node (ref "P2") (pin "18") (pinfunction "18_18") (pintype "passive"))
    )
    (net (code "119") (name "unconnected-(U1A-PA0-Pad10)") (class "Default")
      (node (ref "U1") (pin "10") (pinfunction "PA0_10") (pintype "bidirectional"))
    )
    (net (code "120") (name "unconnected-(U1A-PA1-Pad11)") (class "Default")
      (node (ref "U1") (pin "11") (pinfunction "PA1_11") (pintype "bidirectional"))
    )
    (net (code "121") (name "unconnected-(U1A-PA2-Pad12)") (class "Default")
      (node (ref "U1") (pin "12") (pinfunction "PA2_12") (pintype "bidirectional"))
    )
    (net (code "122") (name "unconnected-(U1A-PA6-Pad16)") (class "Default")
      (node (ref "U1") (pin "16") (pinfunction "PA6_16") (pintype "bidirectional"))
    )
    (net (code "123") (name "unconnected-(U1A-PA8-Pad29)") (class "Default")
      (node (ref "U1") (pin "29") (pinfunction "PA8_29") (pintype "bidirectional"))
    )
    (net (code "124") (name "unconnected-(U1A-PA9-Pad30)") (class "Default")
      (node (ref "U1") (pin "30") (pinfunction "PA9_30") (pintype "bidirectional"))
    )
    (net (code "125") (name "unconnected-(U1A-PA10-Pad31)") (class "Default")
      (node (ref "U1") (pin "31") (pinfunction "PA10_31") (pintype "bidirectional"))
    )
    (net (code "126") (name "unconnected-(U1A-PA11-Pad32)") (class "Default")
      (node (ref "U1") (pin "32") (pinfunction "PA11_32") (pintype "bidirectional"))
    )
    (net (code "127") (name "unconnected-(U1A-PA12-Pad33)") (class "Default")
      (node (ref "U1") (pin "33") (pinfunction "PA12_33") (pintype "bidirectional"))
    )
    (net (code "128") (name "unconnected-(U1A-PA15-Pad38)") (class "Default")
      (node (ref "U1") (pin "38") (pinfunction "PA15_38") (pintype "bidirectional"))
    )
    (net (code "129") (name "unconnected-(U1A-PC13-Pad2)") (class "Default")
      (node (ref "U1") (pin "2") (pinfunction "PC13_2") (pintype "bidirectional"))
    )
    (net (code "130") (name "unconnected-(U1A-PC14{slash}OSC32_IN-Pad3)") (class "Default")
      (node (ref "U1") (pin "3") (pinfunction "PC14/OSC32_IN_3") (pintype "bidirectional"))
    )
    (net (code "131") (name "unconnected-(U1A-PC15{slash}OSC32_OUT-Pad4)") (class "Default")
      (node (ref "U1") (pin "4") (pinfunction "PC15/OSC32_OUT_4") (pintype "bidirectional"))
    )
  )
)
